# car_battery_check.net
KiCad netlist of a schematic drawn in EAGLE
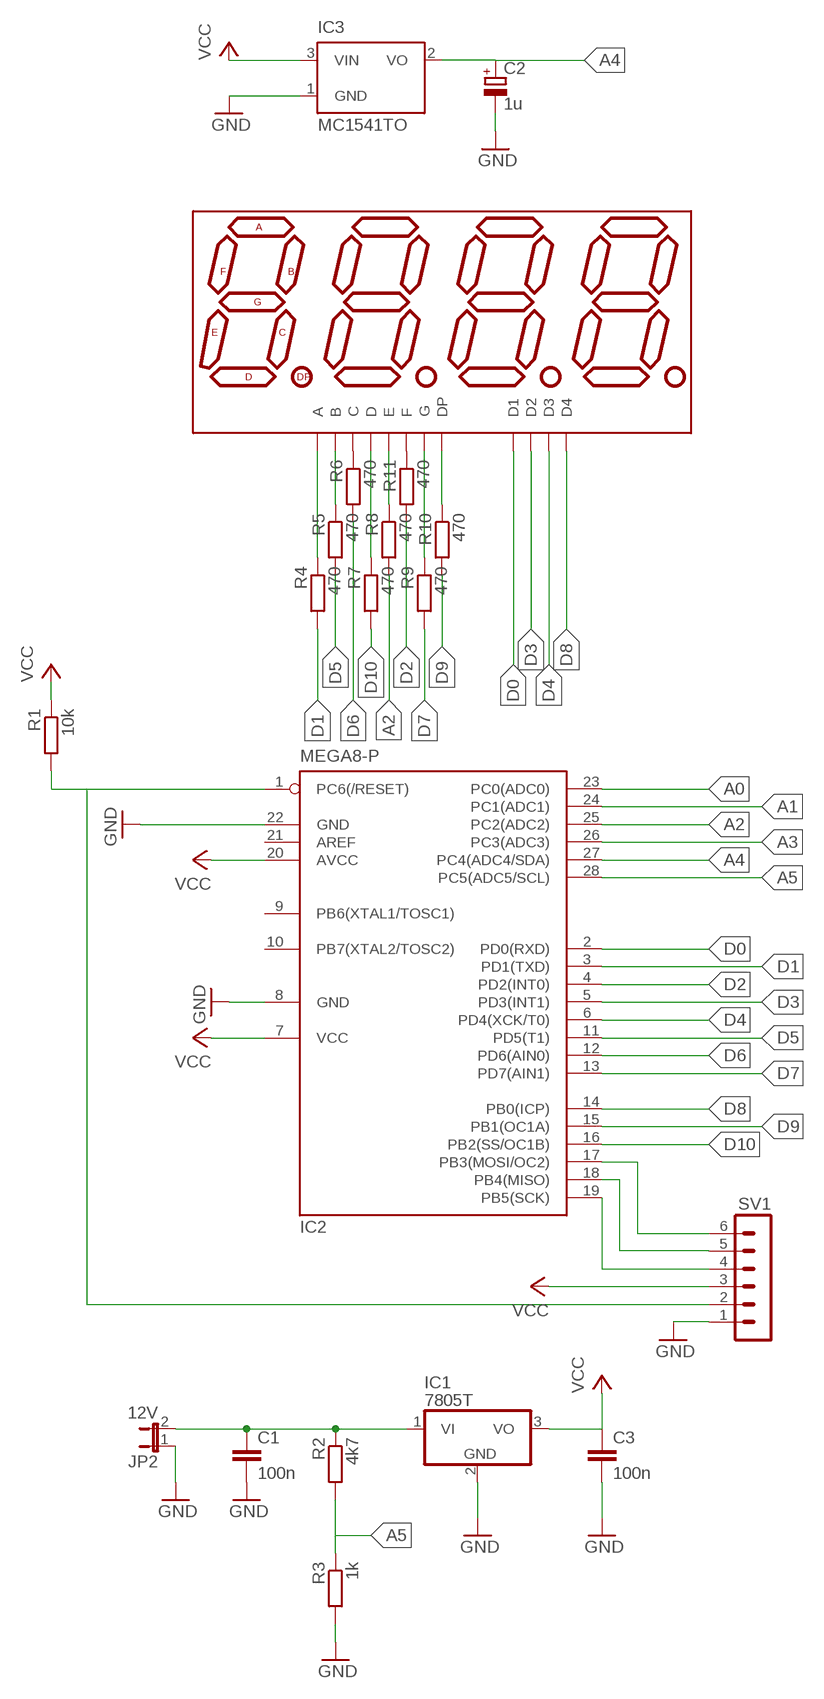
[diagram p0: schematic, sheet 1]

(export (version "E")
  (design (tool "Eeschema 10.0.6"))
  (components
    (comp (ref "C1")
      (value "100n")
      (footprint "eagle-import:C025-024X044")
      (libsource (lib "eagle-import") (part "C-EU025-024X044"))
    )
    (comp (ref "C2")
      (value "1u")
      (footprint "eagle-import:E2,5-6E")
      (libsource (lib "eagle-import") (part "CPOL-EUE2,5-6E"))
    )
    (comp (ref "C3")
      (value "100n")
      (footprint "eagle-import:C025-024X044")
      (libsource (lib "eagle-import") (part "C-EU025-024X044"))
    )
    (comp (ref "IC1")
      (value "7805T")
      (footprint "eagle-import:TO220H")
      (libsource (lib "eagle-import") (part "78T05"))
    )
    (comp (ref "IC2")
      (value "MEGA8-P")
      (footprint "eagle-import:DIL28-3")
      (libsource (lib "eagle-import") (part "MEGA8-P"))
    )
    (comp (ref "IC3")
      (value "MC1541TO")
      (footprint "eagle-import:TO92")
      (libsource (lib "eagle-import") (part "MC15TO41"))
    )
    (comp (ref "JP2")
      (value "12V")
      (footprint "eagle-import:JP1")
      (libsource (lib "eagle-import") (part "JP1E"))
    )
    (comp (ref "R1")
      (value "10k")
      (footprint "eagle-import:0617_17")
      (libsource (lib "eagle-import") (part "R-EU_0617/17"))
    )
    (comp (ref "R2")
      (value "4k7")
      (footprint "eagle-import:R2512")
      (libsource (lib "eagle-import") (part "R-EU_R2512"))
    )
    (comp (ref "R3")
      (value "1k")
      (footprint "eagle-import:0207_15")
      (libsource (lib "eagle-import") (part "R-EU_0207/15"))
    )
    (comp (ref "R4")
      (value "470")
      (footprint "eagle-import:0204_7")
      (libsource (lib "eagle-import") (part "R-EU_0204/7"))
    )
    (comp (ref "R5")
      (value "470")
      (footprint "eagle-import:0207_10")
      (libsource (lib "eagle-import") (part "R-EU_0207/10"))
    )
    (comp (ref "R6")
      (value "470")
      (footprint "eagle-import:0204_7")
      (libsource (lib "eagle-import") (part "R-EU_0204/7"))
    )
    (comp (ref "R7")
      (value "470")
      (footprint "eagle-import:0207_12")
      (libsource (lib "eagle-import") (part "R-EU_0207/12"))
    )
    (comp (ref "R8")
      (value "470")
      (footprint "eagle-import:0207_15")
      (libsource (lib "eagle-import") (part "R-EU_0207/15"))
    )
    (comp (ref "R9")
      (value "470")
      (footprint "eagle-import:0204_7")
      (libsource (lib "eagle-import") (part "R-EU_0204/7"))
    )
    (comp (ref "R10")
      (value "470")
      (footprint "eagle-import:0204_7")
      (libsource (lib "eagle-import") (part "R-EU_0204/7"))
    )
    (comp (ref "R11")
      (value "470")
      (footprint "eagle-import:0204_7")
      (libsource (lib "eagle-import") (part "R-EU_0204/7"))
    )
    (comp (ref "SV1")
      (value "MA06-1")
      (footprint "eagle-import:MA06-1")
      (libsource (lib "eagle-import") (part "MA06-1"))
    )
    (comp (ref "U$1")
      (value "7-SEGMENT-4DIGIT-COUNTERPTH")
      (footprint "eagle-import:7-SEGMENT-4DIGIT-COUNTER")
      (libsource (lib "eagle-import") (part "7-SEGMENT-4DIGIT-COUNTERPTH"))
    )
  )
  (nets
    (net (code "1") (name "A0") (class "Default")
      (node (ref "IC2") (pin "23") (pinfunction "PC0(ADC0)_23") (pintype "bidirectional"))
    )
    (net (code "2") (name "A1") (class "Default")
      (node (ref "IC2") (pin "24") (pinfunction "PC1(ADC1)_24") (pintype "bidirectional"))
    )
    (net (code "3") (name "A2") (class "Default")
      (node (ref "IC2") (pin "25") (pinfunction "PC2(ADC2)_25") (pintype "bidirectional"))
      (node (ref "R8") (pin "2") (pinfunction "2_2") (pintype "passive"))
    )
    (net (code "4") (name "A3") (class "Default")
      (node (ref "IC2") (pin "26") (pinfunction "PC3(ADC3)_26") (pintype "bidirectional"))
    )
    (net (code "5") (name "A4") (class "Default")
      (node (ref "C2") (pin "+") (pinfunction "+_+") (pintype "passive"))
      (node (ref "IC2") (pin "27") (pinfunction "PC4(ADC4/SDA)_27") (pintype "bidirectional"))
      (node (ref "IC3") (pin "2") (pinfunction "VO_2") (pintype "output"))
    )
    (net (code "6") (name "A5") (class "Default")
      (node (ref "IC2") (pin "28") (pinfunction "PC5(ADC5/SCL)_28") (pintype "bidirectional"))
      (node (ref "R2") (pin "2") (pinfunction "2_2") (pintype "passive"))
      (node (ref "R3") (pin "1") (pinfunction "1_1") (pintype "passive"))
    )
    (net (code "7") (name "D0") (class "Default")
      (node (ref "IC2") (pin "2") (pinfunction "PD0(RXD)_2") (pintype "bidirectional"))
      (node (ref "U$1") (pin "12") (pinfunction "D1_12") (pintype "bidirectional"))
    )
    (net (code "8") (name "D1") (class "Default")
      (node (ref "IC2") (pin "3") (pinfunction "PD1(TXD)_3") (pintype "bidirectional"))
      (node (ref "R4") (pin "2") (pinfunction "2_2") (pintype "passive"))
    )
    (net (code "9") (name "D2") (class "Default")
      (node (ref "IC2") (pin "4") (pinfunction "PD2(INT0)_4") (pintype "bidirectional"))
      (node (ref "R11") (pin "2") (pinfunction "2_2") (pintype "passive"))
    )
    (net (code "10") (name "D3") (class "Default")
      (node (ref "IC2") (pin "5") (pinfunction "PD3(INT1)_5") (pintype "bidirectional"))
      (node (ref "U$1") (pin "9") (pinfunction "D2_9") (pintype "bidirectional"))
    )
    (net (code "11") (name "D4") (class "Default")
      (node (ref "IC2") (pin "6") (pinfunction "PD4(XCK/T0)_6") (pintype "bidirectional"))
      (node (ref "U$1") (pin "8") (pinfunction "D3_8") (pintype "bidirectional"))
    )
    (net (code "12") (name "D5") (class "Default")
      (node (ref "IC2") (pin "11") (pinfunction "PD5(T1)_11") (pintype "bidirectional"))
      (node (ref "R5") (pin "2") (pinfunction "2_2") (pintype "passive"))
    )
    (net (code "13") (name "D6") (class "Default")
      (node (ref "IC2") (pin "12") (pinfunction "PD6(AIN0)_12") (pintype "bidirectional"))
      (node (ref "R6") (pin "2") (pinfunction "2_2") (pintype "passive"))
    )
    (net (code "14") (name "D7") (class "Default")
      (node (ref "IC2") (pin "13") (pinfunction "PD7(AIN1)_13") (pintype "bidirectional"))
      (node (ref "R9") (pin "2") (pinfunction "2_2") (pintype "passive"))
    )
    (net (code "15") (name "D8") (class "Default")
      (node (ref "IC2") (pin "14") (pinfunction "PB0(ICP)_14") (pintype "bidirectional"))
      (node (ref "U$1") (pin "6") (pinfunction "D4_6") (pintype "bidirectional"))
    )
    (net (code "16") (name "D9") (class "Default")
      (node (ref "IC2") (pin "15") (pinfunction "PB1(OC1A)_15") (pintype "bidirectional"))
      (node (ref "R10") (pin "2") (pinfunction "2_2") (pintype "passive"))
    )
    (net (code "17") (name "D10") (class "Default")
      (node (ref "IC2") (pin "16") (pinfunction "PB2(SS/OC1B)_16") (pintype "bidirectional"))
      (node (ref "R7") (pin "2") (pinfunction "2_2") (pintype "passive"))
    )
    (net (code "18") (name "GND") (class "Default")
      (node (ref "C1") (pin "2") (pinfunction "2_2") (pintype "passive"))
      (node (ref "C2") (pin "-") (pinfunction "-_-") (pintype "passive"))
      (node (ref "C3") (pin "2") (pinfunction "2_2") (pintype "passive"))
      (node (ref "IC1") (pin "2") (pinfunction "GND_2") (pintype "passive"))
      (node (ref "IC2") (pin "22") (pinfunction "GND_22") (pintype "power_in"))
      (node (ref "IC2") (pin "8") (pinfunction "GND_8") (pintype "power_in"))
      (node (ref "IC3") (pin "1") (pinfunction "GND_1") (pintype "passive"))
      (node (ref "JP2") (pin "1") (pinfunction "1_1") (pintype "passive"))
      (node (ref "R3") (pin "2") (pinfunction "2_2") (pintype "passive"))
      (node (ref "SV1") (pin "1") (pinfunction "1_1") (pintype "passive"))
    )
    (net (code "19") (name "Net-(IC1-VI)") (class "Default")
      (node (ref "C1") (pin "1") (pinfunction "1_1") (pintype "passive"))
      (node (ref "IC1") (pin "1") (pinfunction "VI_1") (pintype "input"))
      (node (ref "JP2") (pin "2") (pinfunction "2_2") (pintype "passive"))
      (node (ref "R2") (pin "1") (pinfunction "1_1") (pintype "passive"))
    )
    (net (code "20") (name "Net-(IC2-PB3(MOSI{slash}OC2))") (class "Default")
      (node (ref "IC2") (pin "17") (pinfunction "PB3(MOSI/OC2)_17") (pintype "bidirectional"))
      (node (ref "SV1") (pin "6") (pinfunction "6_6") (pintype "passive"))
    )
    (net (code "21") (name "Net-(IC2-PB4(MISO))") (class "Default")
      (node (ref "IC2") (pin "18") (pinfunction "PB4(MISO)_18") (pintype "bidirectional"))
      (node (ref "SV1") (pin "5") (pinfunction "5_5") (pintype "passive"))
    )
    (net (code "22") (name "Net-(IC2-PB5(SCK))") (class "Default")
      (node (ref "IC2") (pin "19") (pinfunction "PB5(SCK)_19") (pintype "bidirectional"))
      (node (ref "SV1") (pin "4") (pinfunction "4_4") (pintype "passive"))
    )
    (net (code "23") (name "Net-(IC2-PC6({slash}RESET))") (class "Default")
      (node (ref "IC2") (pin "1") (pinfunction "PC6(/RESET)_1") (pintype "bidirectional"))
      (node (ref "R1") (pin "2") (pinfunction "2_2") (pintype "passive"))
      (node (ref "SV1") (pin "2") (pinfunction "2_2") (pintype "passive"))
    )
    (net (code "24") (name "Net-(U$1-A)") (class "Default")
      (node (ref "R4") (pin "1") (pinfunction "1_1") (pintype "passive"))
      (node (ref "U$1") (pin "11") (pinfunction "A_11") (pintype "bidirectional"))
    )
    (net (code "25") (name "Net-(U$1-B)") (class "Default")
      (node (ref "R5") (pin "1") (pinfunction "1_1") (pintype "passive"))
      (node (ref "U$1") (pin "7") (pinfunction "B_7") (pintype "bidirectional"))
    )
    (net (code "26") (name "Net-(U$1-C)") (class "Default")
      (node (ref "R6") (pin "1") (pinfunction "1_1") (pintype "passive"))
      (node (ref "U$1") (pin "4") (pinfunction "C_4") (pintype "bidirectional"))
    )
    (net (code "27") (name "Net-(U$1-D)") (class "Default")
      (node (ref "R7") (pin "1") (pinfunction "1_1") (pintype "passive"))
      (node (ref "U$1") (pin "2") (pinfunction "D_2") (pintype "bidirectional"))
    )
    (net (code "28") (name "Net-(U$1-DP)") (class "Default")
      (node (ref "R10") (pin "1") (pinfunction "1_1") (pintype "passive"))
      (node (ref "U$1") (pin "3") (pinfunction "DP_3") (pintype "bidirectional"))
    )
    (net (code "29") (name "Net-(U$1-E)") (class "Default")
      (node (ref "R8") (pin "1") (pinfunction "1_1") (pintype "passive"))
      (node (ref "U$1") (pin "1") (pinfunction "E_1") (pintype "bidirectional"))
    )
    (net (code "30") (name "Net-(U$1-F)") (class "Default")
      (node (ref "R11") (pin "1") (pinfunction "1_1") (pintype "passive"))
      (node (ref "U$1") (pin "10") (pinfunction "F_10") (pintype "bidirectional"))
    )
    (net (code "31") (name "Net-(U$1-G)") (class "Default")
      (node (ref "R9") (pin "1") (pinfunction "1_1") (pintype "passive"))
      (node (ref "U$1") (pin "5") (pinfunction "G_5") (pintype "bidirectional"))
    )
    (net (code "32") (name "VCC") (class "Default")
      (node (ref "C3") (pin "1") (pinfunction "1_1") (pintype "passive"))
      (node (ref "IC1") (pin "3") (pinfunction "VO_3") (pintype "passive"))
      (node (ref "IC2") (pin "20") (pinfunction "AVCC_20") (pintype "power_in"))
      (node (ref "IC2") (pin "7") (pinfunction "VCC_7") (pintype "power_in"))
      (node (ref "IC3") (pin "3") (pinfunction "VIN_3") (pintype "input"))
      (node (ref "R1") (pin "1") (pinfunction "1_1") (pintype "passive"))
      (node (ref "SV1") (pin "3") (pinfunction "3_3") (pintype "passive"))
    )
    (net (code "33") (name "unconnected-(IC2-AREF-Pad21)") (class "Default")
      (node (ref "IC2") (pin "21") (pinfunction "AREF_21") (pintype "passive"))
    )
    (net (code "34") (name "unconnected-(IC2-PB6(XTAL1{slash}TOSC1)-Pad9)") (class "Default")
      (node (ref "IC2") (pin "9") (pinfunction "PB6(XTAL1/TOSC1)_9") (pintype "bidirectional"))
    )
    (net (code "35") (name "unconnected-(IC2-PB7(XTAL2{slash}TOSC2)-Pad10)") (class "Default")
      (node (ref "IC2") (pin "10") (pinfunction "PB7(XTAL2/TOSC2)_10") (pintype "bidirectional"))
    )
  )
)
